# PiArcadeGPIO.net
KiCad netlist of a schematic drawn in Altium Designer
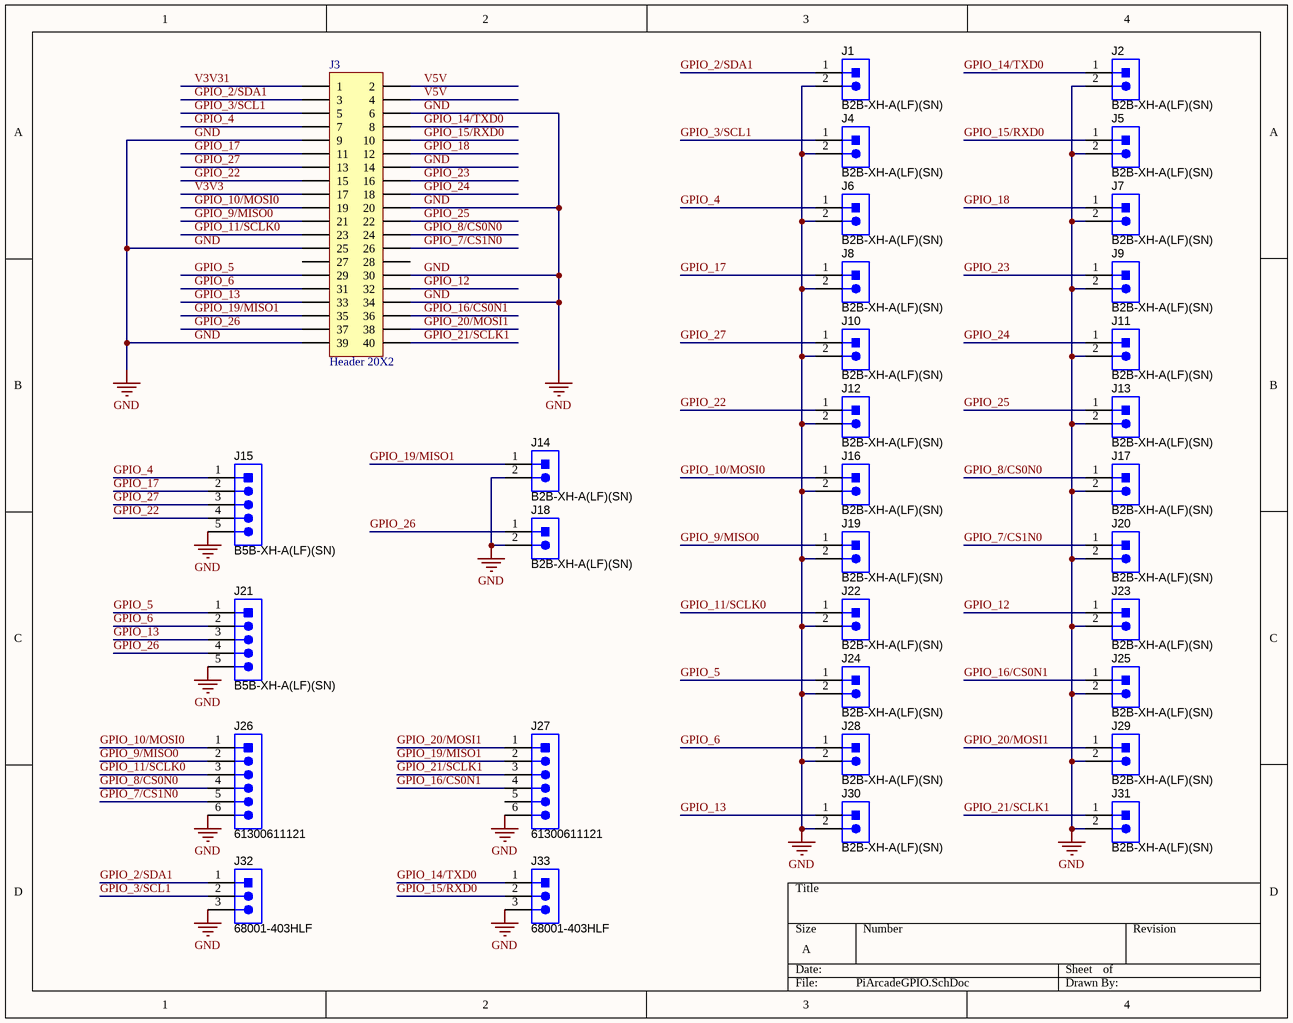
[diagram p0: PiArcadeGPIO.SchDoc]

(export (version "E")
  (design (tool "Eeschema 10.0.6"))
  (components
    (comp (ref "J1")
      (value "B2B-XH-A(LF)(SN)")
      (footprint "JST_B2B-XH-A")
      (description "Header (Shrouded), 2.5mm, 2x1, Tin, TH")
      (fields
        (field (name "MANUFACTURER") "JST Manufacturing")
        (field (name "SYMBOLCREATOR") "a0412235")
        (field (name "PUBLISHER") "Texas Instruments")
      )
      (libsource (lib "Connectors_Other") (part "B2B-XH-A(LF)(SN)"))
    )
    (comp (ref "J2")
      (value "B2B-XH-A(LF)(SN)")
      (footprint "JST_B2B-XH-A")
      (description "Header (Shrouded), 2.5mm, 2x1, Tin, TH")
      (fields
        (field (name "MANUFACTURER") "JST Manufacturing")
        (field (name "SYMBOLCREATOR") "a0412235")
        (field (name "PUBLISHER") "Texas Instruments")
      )
      (libsource (lib "Connectors_Other") (part "B2B-XH-A(LF)(SN)"))
    )
    (comp (ref "J3")
      (value "Header 20X2")
      (footprint "HDR2X20")
      (description "Header, 20-Pin, Dual row")
      (fields (field (name "PUBLISHER") "Altium Limited"))
      (libsource (lib "Miscellaneous Connectors") (part "Header 20X2"))
    )
    (comp (ref "J4")
      (value "B2B-XH-A(LF)(SN)")
      (footprint "JST_B2B-XH-A")
      (description "Header (Shrouded), 2.5mm, 2x1, Tin, TH")
      (fields
        (field (name "MANUFACTURER") "JST Manufacturing")
        (field (name "SYMBOLCREATOR") "a0412235")
        (field (name "PUBLISHER") "Texas Instruments")
      )
      (libsource (lib "Connectors_Other") (part "B2B-XH-A(LF)(SN)"))
    )
    (comp (ref "J5")
      (value "B2B-XH-A(LF)(SN)")
      (footprint "JST_B2B-XH-A")
      (description "Header (Shrouded), 2.5mm, 2x1, Tin, TH")
      (fields
        (field (name "MANUFACTURER") "JST Manufacturing")
        (field (name "SYMBOLCREATOR") "a0412235")
        (field (name "PUBLISHER") "Texas Instruments")
      )
      (libsource (lib "Connectors_Other") (part "B2B-XH-A(LF)(SN)"))
    )
    (comp (ref "J6")
      (value "B2B-XH-A(LF)(SN)")
      (footprint "JST_B2B-XH-A")
      (description "Header (Shrouded), 2.5mm, 2x1, Tin, TH")
      (fields
        (field (name "MANUFACTURER") "JST Manufacturing")
        (field (name "SYMBOLCREATOR") "a0412235")
        (field (name "PUBLISHER") "Texas Instruments")
      )
      (libsource (lib "Connectors_Other") (part "B2B-XH-A(LF)(SN)"))
    )
    (comp (ref "J7")
      (value "B2B-XH-A(LF)(SN)")
      (footprint "JST_B2B-XH-A")
      (description "Header (Shrouded), 2.5mm, 2x1, Tin, TH")
      (fields
        (field (name "MANUFACTURER") "JST Manufacturing")
        (field (name "SYMBOLCREATOR") "a0412235")
        (field (name "PUBLISHER") "Texas Instruments")
      )
      (libsource (lib "Connectors_Other") (part "B2B-XH-A(LF)(SN)"))
    )
    (comp (ref "J8")
      (value "B2B-XH-A(LF)(SN)")
      (footprint "JST_B2B-XH-A")
      (description "Header (Shrouded), 2.5mm, 2x1, Tin, TH")
      (fields
        (field (name "MANUFACTURER") "JST Manufacturing")
        (field (name "SYMBOLCREATOR") "a0412235")
        (field (name "PUBLISHER") "Texas Instruments")
      )
      (libsource (lib "Connectors_Other") (part "B2B-XH-A(LF)(SN)"))
    )
    (comp (ref "J9")
      (value "B2B-XH-A(LF)(SN)")
      (footprint "JST_B2B-XH-A")
      (description "Header (Shrouded), 2.5mm, 2x1, Tin, TH")
      (fields
        (field (name "MANUFACTURER") "JST Manufacturing")
        (field (name "SYMBOLCREATOR") "a0412235")
        (field (name "PUBLISHER") "Texas Instruments")
      )
      (libsource (lib "Connectors_Other") (part "B2B-XH-A(LF)(SN)"))
    )
    (comp (ref "J10")
      (value "B2B-XH-A(LF)(SN)")
      (footprint "JST_B2B-XH-A")
      (description "Header (Shrouded), 2.5mm, 2x1, Tin, TH")
      (fields
        (field (name "MANUFACTURER") "JST Manufacturing")
        (field (name "SYMBOLCREATOR") "a0412235")
        (field (name "PUBLISHER") "Texas Instruments")
      )
      (libsource (lib "Connectors_Other") (part "B2B-XH-A(LF)(SN)"))
    )
    (comp (ref "J11")
      (value "B2B-XH-A(LF)(SN)")
      (footprint "JST_B2B-XH-A")
      (description "Header (Shrouded), 2.5mm, 2x1, Tin, TH")
      (fields
        (field (name "MANUFACTURER") "JST Manufacturing")
        (field (name "SYMBOLCREATOR") "a0412235")
        (field (name "PUBLISHER") "Texas Instruments")
      )
      (libsource (lib "Connectors_Other") (part "B2B-XH-A(LF)(SN)"))
    )
    (comp (ref "J12")
      (value "B2B-XH-A(LF)(SN)")
      (footprint "JST_B2B-XH-A")
      (description "Header (Shrouded), 2.5mm, 2x1, Tin, TH")
      (fields
        (field (name "MANUFACTURER") "JST Manufacturing")
        (field (name "SYMBOLCREATOR") "a0412235")
        (field (name "PUBLISHER") "Texas Instruments")
      )
      (libsource (lib "Connectors_Other") (part "B2B-XH-A(LF)(SN)"))
    )
    (comp (ref "J13")
      (value "B2B-XH-A(LF)(SN)")
      (footprint "JST_B2B-XH-A")
      (description "Header (Shrouded), 2.5mm, 2x1, Tin, TH")
      (fields
        (field (name "MANUFACTURER") "JST Manufacturing")
        (field (name "SYMBOLCREATOR") "a0412235")
        (field (name "PUBLISHER") "Texas Instruments")
      )
      (libsource (lib "Connectors_Other") (part "B2B-XH-A(LF)(SN)"))
    )
    (comp (ref "J14")
      (value "B2B-XH-A(LF)(SN)")
      (footprint "JST_B2B-XH-A")
      (description "Header (Shrouded), 2.5mm, 2x1, Tin, TH")
      (fields
        (field (name "MANUFACTURER") "JST Manufacturing")
        (field (name "SYMBOLCREATOR") "a0412235")
        (field (name "PUBLISHER") "Texas Instruments")
      )
      (libsource (lib "Connectors_Other") (part "B2B-XH-A(LF)(SN)"))
    )
    (comp (ref "J15")
      (value "B5B-XH-A(LF)(SN)")
      (footprint "JST_B5B-XH-A")
      (description "Header(shrouded), 2.5mm, 5x1, Tin, TH")
      (fields
        (field (name "MANUFACTURER") "JST Manufacturing")
        (field (name "SYMBOLCREATOR") "a0412235")
        (field (name "PUBLISHER") "Texas Instruments")
      )
      (libsource (lib "Connectors_Other") (part "B5B-XH-A(LF)(SN)"))
    )
    (comp (ref "J16")
      (value "B2B-XH-A(LF)(SN)")
      (footprint "JST_B2B-XH-A")
      (description "Header (Shrouded), 2.5mm, 2x1, Tin, TH")
      (fields
        (field (name "MANUFACTURER") "JST Manufacturing")
        (field (name "SYMBOLCREATOR") "a0412235")
        (field (name "PUBLISHER") "Texas Instruments")
      )
      (libsource (lib "Connectors_Other") (part "B2B-XH-A(LF)(SN)"))
    )
    (comp (ref "J17")
      (value "B2B-XH-A(LF)(SN)")
      (footprint "JST_B2B-XH-A")
      (description "Header (Shrouded), 2.5mm, 2x1, Tin, TH")
      (fields
        (field (name "MANUFACTURER") "JST Manufacturing")
        (field (name "SYMBOLCREATOR") "a0412235")
        (field (name "PUBLISHER") "Texas Instruments")
      )
      (libsource (lib "Connectors_Other") (part "B2B-XH-A(LF)(SN)"))
    )
    (comp (ref "J18")
      (value "B2B-XH-A(LF)(SN)")
      (footprint "JST_B2B-XH-A")
      (description "Header (Shrouded), 2.5mm, 2x1, Tin, TH")
      (fields
        (field (name "MANUFACTURER") "JST Manufacturing")
        (field (name "SYMBOLCREATOR") "a0412235")
        (field (name "PUBLISHER") "Texas Instruments")
      )
      (libsource (lib "Connectors_Other") (part "B2B-XH-A(LF)(SN)"))
    )
    (comp (ref "J19")
      (value "B2B-XH-A(LF)(SN)")
      (footprint "JST_B2B-XH-A")
      (description "Header (Shrouded), 2.5mm, 2x1, Tin, TH")
      (fields
        (field (name "MANUFACTURER") "JST Manufacturing")
        (field (name "SYMBOLCREATOR") "a0412235")
        (field (name "PUBLISHER") "Texas Instruments")
      )
      (libsource (lib "Connectors_Other") (part "B2B-XH-A(LF)(SN)"))
    )
    (comp (ref "J20")
      (value "B2B-XH-A(LF)(SN)")
      (footprint "JST_B2B-XH-A")
      (description "Header (Shrouded), 2.5mm, 2x1, Tin, TH")
      (fields
        (field (name "MANUFACTURER") "JST Manufacturing")
        (field (name "SYMBOLCREATOR") "a0412235")
        (field (name "PUBLISHER") "Texas Instruments")
      )
      (libsource (lib "Connectors_Other") (part "B2B-XH-A(LF)(SN)"))
    )
    (comp (ref "J21")
      (value "B5B-XH-A(LF)(SN)")
      (footprint "JST_B5B-XH-A")
      (description "Header(shrouded), 2.5mm, 5x1, Tin, TH")
      (fields
        (field (name "MANUFACTURER") "JST Manufacturing")
        (field (name "SYMBOLCREATOR") "a0412235")
        (field (name "PUBLISHER") "Texas Instruments")
      )
      (libsource (lib "Connectors_Other") (part "B5B-XH-A(LF)(SN)"))
    )
    (comp (ref "J22")
      (value "B2B-XH-A(LF)(SN)")
      (footprint "JST_B2B-XH-A")
      (description "Header (Shrouded), 2.5mm, 2x1, Tin, TH")
      (fields
        (field (name "MANUFACTURER") "JST Manufacturing")
        (field (name "SYMBOLCREATOR") "a0412235")
        (field (name "PUBLISHER") "Texas Instruments")
      )
      (libsource (lib "Connectors_Other") (part "B2B-XH-A(LF)(SN)"))
    )
    (comp (ref "J23")
      (value "B2B-XH-A(LF)(SN)")
      (footprint "JST_B2B-XH-A")
      (description "Header (Shrouded), 2.5mm, 2x1, Tin, TH")
      (fields
        (field (name "MANUFACTURER") "JST Manufacturing")
        (field (name "SYMBOLCREATOR") "a0412235")
        (field (name "PUBLISHER") "Texas Instruments")
      )
      (libsource (lib "Connectors_Other") (part "B2B-XH-A(LF)(SN)"))
    )
    (comp (ref "J24")
      (value "B2B-XH-A(LF)(SN)")
      (footprint "JST_B2B-XH-A")
      (description "Header (Shrouded), 2.5mm, 2x1, Tin, TH")
      (fields
        (field (name "MANUFACTURER") "JST Manufacturing")
        (field (name "SYMBOLCREATOR") "a0412235")
        (field (name "PUBLISHER") "Texas Instruments")
      )
      (libsource (lib "Connectors_Other") (part "B2B-XH-A(LF)(SN)"))
    )
    (comp (ref "J25")
      (value "B2B-XH-A(LF)(SN)")
      (footprint "JST_B2B-XH-A")
      (description "Header (Shrouded), 2.5mm, 2x1, Tin, TH")
      (fields
        (field (name "MANUFACTURER") "JST Manufacturing")
        (field (name "SYMBOLCREATOR") "a0412235")
        (field (name "PUBLISHER") "Texas Instruments")
      )
      (libsource (lib "Connectors_Other") (part "B2B-XH-A(LF)(SN)"))
    )
    (comp (ref "J26")
      (value "61300611121")
      (footprint "WURTH_61300611121")
      (description "Header, 2.54 mm, 6x1, Gold, TH")
      (fields
        (field (name "MANUFACTURER") "Wurth Elektronik")
        (field (name "SYMBOLCREATOR") "a0412235")
        (field (name "PUBLISHER") "Texas Instruments")
      )
      (libsource (lib "Connectors_Other") (part "61300611121"))
    )
    (comp (ref "J27")
      (value "61300611121")
      (footprint "WURTH_61300611121")
      (description "Header, 2.54 mm, 6x1, Gold, TH")
      (fields
        (field (name "MANUFACTURER") "Wurth Elektronik")
        (field (name "SYMBOLCREATOR") "a0412235")
        (field (name "PUBLISHER") "Texas Instruments")
      )
      (libsource (lib "Connectors_Other") (part "61300611121"))
    )
    (comp (ref "J28")
      (value "B2B-XH-A(LF)(SN)")
      (footprint "JST_B2B-XH-A")
      (description "Header (Shrouded), 2.5mm, 2x1, Tin, TH")
      (fields
        (field (name "MANUFACTURER") "JST Manufacturing")
        (field (name "SYMBOLCREATOR") "a0412235")
        (field (name "PUBLISHER") "Texas Instruments")
      )
      (libsource (lib "Connectors_Other") (part "B2B-XH-A(LF)(SN)"))
    )
    (comp (ref "J29")
      (value "B2B-XH-A(LF)(SN)")
      (footprint "JST_B2B-XH-A")
      (description "Header (Shrouded), 2.5mm, 2x1, Tin, TH")
      (fields
        (field (name "MANUFACTURER") "JST Manufacturing")
        (field (name "SYMBOLCREATOR") "a0412235")
        (field (name "PUBLISHER") "Texas Instruments")
      )
      (libsource (lib "Connectors_Other") (part "B2B-XH-A(LF)(SN)"))
    )
    (comp (ref "J30")
      (value "B2B-XH-A(LF)(SN)")
      (footprint "JST_B2B-XH-A")
      (description "Header (Shrouded), 2.5mm, 2x1, Tin, TH")
      (fields
        (field (name "MANUFACTURER") "JST Manufacturing")
        (field (name "SYMBOLCREATOR") "a0412235")
        (field (name "PUBLISHER") "Texas Instruments")
      )
      (libsource (lib "Connectors_Other") (part "B2B-XH-A(LF)(SN)"))
    )
    (comp (ref "J31")
      (value "B2B-XH-A(LF)(SN)")
      (footprint "JST_B2B-XH-A")
      (description "Header (Shrouded), 2.5mm, 2x1, Tin, TH")
      (fields
        (field (name "MANUFACTURER") "JST Manufacturing")
        (field (name "SYMBOLCREATOR") "a0412235")
        (field (name "PUBLISHER") "Texas Instruments")
      )
      (libsource (lib "Connectors_Other") (part "B2B-XH-A(LF)(SN)"))
    )
    (comp (ref "J32")
      (value "68001-403HLF")
      (footprint "FCI_68001-403HLF")
      (description "Header, 2.54mm, 3x1, Tin, TH")
      (fields
        (field (name "MANUFACTURER") "FCI")
        (field (name "SYMBOLCREATOR") "a0799628")
        (field (name "PUBLISHER") "Texas Instruments")
      )
      (libsource (lib "Connectors_Other") (part "68001-403HLF"))
    )
    (comp (ref "J33")
      (value "68001-403HLF")
      (footprint "FCI_68001-403HLF")
      (description "Header, 2.54mm, 3x1, Tin, TH")
      (fields
        (field (name "MANUFACTURER") "FCI")
        (field (name "SYMBOLCREATOR") "a0799628")
        (field (name "PUBLISHER") "Texas Instruments")
      )
      (libsource (lib "Connectors_Other") (part "68001-403HLF"))
    )
  )
  (nets
    (net (code "1") (name "/GPIO_2{slash}SDA1") (class "Default")
      (node (ref "J1") (pin "1") (pinfunction "1_1") (pintype "passive"))
      (node (ref "J3") (pin "3") (pinfunction "3_3") (pintype "passive"))
      (node (ref "J32") (pin "1") (pinfunction "1_1") (pintype "passive"))
    )
    (net (code "2") (name "/GPIO_3{slash}SCL1") (class "Default")
      (node (ref "J3") (pin "5") (pinfunction "5_5") (pintype "passive"))
      (node (ref "J32") (pin "2") (pinfunction "2_2") (pintype "passive"))
      (node (ref "J4") (pin "1") (pinfunction "1_1") (pintype "passive"))
    )
    (net (code "3") (name "/GPIO_4") (class "Default")
      (node (ref "J15") (pin "1") (pinfunction "1_1") (pintype "passive"))
      (node (ref "J3") (pin "7") (pinfunction "7_7") (pintype "passive"))
      (node (ref "J6") (pin "1") (pinfunction "1_1") (pintype "passive"))
    )
    (net (code "4") (name "/GPIO_5") (class "Default")
      (node (ref "J21") (pin "1") (pinfunction "1_1") (pintype "passive"))
      (node (ref "J24") (pin "1") (pinfunction "1_1") (pintype "passive"))
      (node (ref "J3") (pin "29") (pinfunction "29_29") (pintype "passive"))
    )
    (net (code "5") (name "/GPIO_6") (class "Default")
      (node (ref "J21") (pin "2") (pinfunction "2_2") (pintype "passive"))
      (node (ref "J28") (pin "1") (pinfunction "1_1") (pintype "passive"))
      (node (ref "J3") (pin "31") (pinfunction "31_31") (pintype "passive"))
    )
    (net (code "6") (name "/GPIO_7{slash}CS1N0") (class "Default")
      (node (ref "J20") (pin "1") (pinfunction "1_1") (pintype "passive"))
      (node (ref "J26") (pin "5") (pinfunction "5_5") (pintype "passive"))
      (node (ref "J3") (pin "26") (pinfunction "26_26") (pintype "passive"))
    )
    (net (code "7") (name "/GPIO_8{slash}CS0N0") (class "Default")
      (node (ref "J17") (pin "1") (pinfunction "1_1") (pintype "passive"))
      (node (ref "J26") (pin "4") (pinfunction "4_4") (pintype "passive"))
      (node (ref "J3") (pin "24") (pinfunction "24_24") (pintype "passive"))
    )
    (net (code "8") (name "/GPIO_9{slash}MISO0") (class "Default")
      (node (ref "J19") (pin "1") (pinfunction "1_1") (pintype "passive"))
      (node (ref "J26") (pin "2") (pinfunction "2_2") (pintype "passive"))
      (node (ref "J3") (pin "21") (pinfunction "21_21") (pintype "passive"))
    )
    (net (code "9") (name "/GPIO_10{slash}MOSI0") (class "Default")
      (node (ref "J16") (pin "1") (pinfunction "1_1") (pintype "passive"))
      (node (ref "J26") (pin "1") (pinfunction "1_1") (pintype "passive"))
      (node (ref "J3") (pin "19") (pinfunction "19_19") (pintype "passive"))
    )
    (net (code "10") (name "/GPIO_11{slash}SCLK0") (class "Default")
      (node (ref "J22") (pin "1") (pinfunction "1_1") (pintype "passive"))
      (node (ref "J26") (pin "3") (pinfunction "3_3") (pintype "passive"))
      (node (ref "J3") (pin "23") (pinfunction "23_23") (pintype "passive"))
    )
    (net (code "11") (name "/GPIO_12") (class "Default")
      (node (ref "J23") (pin "1") (pinfunction "1_1") (pintype "passive"))
      (node (ref "J3") (pin "32") (pinfunction "32_32") (pintype "passive"))
    )
    (net (code "12") (name "/GPIO_13") (class "Default")
      (node (ref "J21") (pin "3") (pinfunction "3_3") (pintype "passive"))
      (node (ref "J3") (pin "33") (pinfunction "33_33") (pintype "passive"))
      (node (ref "J30") (pin "1") (pinfunction "1_1") (pintype "passive"))
    )
    (net (code "13") (name "/GPIO_14{slash}TXD0") (class "Default")
      (node (ref "J2") (pin "1") (pinfunction "1_1") (pintype "passive"))
      (node (ref "J3") (pin "8") (pinfunction "8_8") (pintype "passive"))
      (node (ref "J33") (pin "1") (pinfunction "1_1") (pintype "passive"))
    )
    (net (code "14") (name "/GPIO_15{slash}RXD0") (class "Default")
      (node (ref "J3") (pin "10") (pinfunction "10_10") (pintype "passive"))
      (node (ref "J33") (pin "2") (pinfunction "2_2") (pintype "passive"))
      (node (ref "J5") (pin "1") (pinfunction "1_1") (pintype "passive"))
    )
    (net (code "15") (name "/GPIO_16{slash}CS0N1") (class "Default")
      (node (ref "J25") (pin "1") (pinfunction "1_1") (pintype "passive"))
      (node (ref "J27") (pin "4") (pinfunction "4_4") (pintype "passive"))
      (node (ref "J3") (pin "36") (pinfunction "36_36") (pintype "passive"))
    )
    (net (code "16") (name "/GPIO_17") (class "Default")
      (node (ref "J15") (pin "2") (pinfunction "2_2") (pintype "passive"))
      (node (ref "J3") (pin "11") (pinfunction "11_11") (pintype "passive"))
      (node (ref "J8") (pin "1") (pinfunction "1_1") (pintype "passive"))
    )
    (net (code "17") (name "/GPIO_18") (class "Default")
      (node (ref "J3") (pin "12") (pinfunction "12_12") (pintype "passive"))
      (node (ref "J7") (pin "1") (pinfunction "1_1") (pintype "passive"))
    )
    (net (code "18") (name "/GPIO_19{slash}MISO1") (class "Default")
      (node (ref "J14") (pin "1") (pinfunction "1_1") (pintype "passive"))
      (node (ref "J27") (pin "2") (pinfunction "2_2") (pintype "passive"))
      (node (ref "J3") (pin "35") (pinfunction "35_35") (pintype "passive"))
    )
    (net (code "19") (name "/GPIO_20{slash}MOSI1") (class "Default")
      (node (ref "J27") (pin "1") (pinfunction "1_1") (pintype "passive"))
      (node (ref "J29") (pin "1") (pinfunction "1_1") (pintype "passive"))
      (node (ref "J3") (pin "38") (pinfunction "38_38") (pintype "passive"))
    )
    (net (code "20") (name "/GPIO_21{slash}SCLK1") (class "Default")
      (node (ref "J27") (pin "3") (pinfunction "3_3") (pintype "passive"))
      (node (ref "J3") (pin "40") (pinfunction "40_40") (pintype "passive"))
      (node (ref "J31") (pin "1") (pinfunction "1_1") (pintype "passive"))
    )
    (net (code "21") (name "/GPIO_22") (class "Default")
      (node (ref "J12") (pin "1") (pinfunction "1_1") (pintype "passive"))
      (node (ref "J15") (pin "4") (pinfunction "4_4") (pintype "passive"))
      (node (ref "J3") (pin "15") (pinfunction "15_15") (pintype "passive"))
    )
    (net (code "22") (name "/GPIO_23") (class "Default")
      (node (ref "J3") (pin "16") (pinfunction "16_16") (pintype "passive"))
      (node (ref "J9") (pin "1") (pinfunction "1_1") (pintype "passive"))
    )
    (net (code "23") (name "/GPIO_24") (class "Default")
      (node (ref "J11") (pin "1") (pinfunction "1_1") (pintype "passive"))
      (node (ref "J3") (pin "18") (pinfunction "18_18") (pintype "passive"))
    )
    (net (code "24") (name "/GPIO_25") (class "Default")
      (node (ref "J13") (pin "1") (pinfunction "1_1") (pintype "passive"))
      (node (ref "J3") (pin "22") (pinfunction "22_22") (pintype "passive"))
    )
    (net (code "25") (name "/GPIO_26") (class "Default")
      (node (ref "J18") (pin "1") (pinfunction "1_1") (pintype "passive"))
      (node (ref "J21") (pin "4") (pinfunction "4_4") (pintype "passive"))
      (node (ref "J3") (pin "37") (pinfunction "37_37") (pintype "passive"))
    )
    (net (code "26") (name "/GPIO_27") (class "Default")
      (node (ref "J10") (pin "1") (pinfunction "1_1") (pintype "passive"))
      (node (ref "J15") (pin "3") (pinfunction "3_3") (pintype "passive"))
      (node (ref "J3") (pin "13") (pinfunction "13_13") (pintype "passive"))
    )
    (net (code "27") (name "/V3V3") (class "Default")
      (node (ref "J3") (pin "17") (pinfunction "17_17") (pintype "passive"))
    )
    (net (code "28") (name "/V3V31") (class "Default")
      (node (ref "J3") (pin "1") (pinfunction "1_1") (pintype "passive"))
    )
    (net (code "29") (name "/V5V") (class "Default")
      (node (ref "J3") (pin "2") (pinfunction "2_2") (pintype "passive"))
      (node (ref "J3") (pin "4") (pinfunction "4_4") (pintype "passive"))
    )
    (net (code "30") (name "GND") (class "Default")
      (node (ref "J1") (pin "2") (pinfunction "2_2") (pintype "passive"))
      (node (ref "J10") (pin "2") (pinfunction "2_2") (pintype "passive"))
      (node (ref "J11") (pin "2") (pinfunction "2_2") (pintype "passive"))
      (node (ref "J12") (pin "2") (pinfunction "2_2") (pintype "passive"))
      (node (ref "J13") (pin "2") (pinfunction "2_2") (pintype "passive"))
      (node (ref "J14") (pin "2") (pinfunction "2_2") (pintype "passive"))
      (node (ref "J15") (pin "5") (pinfunction "5_5") (pintype "passive"))
      (node (ref "J16") (pin "2") (pinfunction "2_2") (pintype "passive"))
      (node (ref "J17") (pin "2") (pinfunction "2_2") (pintype "passive"))
      (node (ref "J18") (pin "2") (pinfunction "2_2") (pintype "passive"))
      (node (ref "J19") (pin "2") (pinfunction "2_2") (pintype "passive"))
      (node (ref "J2") (pin "2") (pinfunction "2_2") (pintype "passive"))
      (node (ref "J20") (pin "2") (pinfunction "2_2") (pintype "passive"))
      (node (ref "J21") (pin "5") (pinfunction "5_5") (pintype "passive"))
      (node (ref "J22") (pin "2") (pinfunction "2_2") (pintype "passive"))
      (node (ref "J23") (pin "2") (pinfunction "2_2") (pintype "passive"))
      (node (ref "J24") (pin "2") (pinfunction "2_2") (pintype "passive"))
      (node (ref "J25") (pin "2") (pinfunction "2_2") (pintype "passive"))
      (node (ref "J26") (pin "6") (pinfunction "6_6") (pintype "passive"))
      (node (ref "J27") (pin "6") (pinfunction "6_6") (pintype "passive"))
      (node (ref "J28") (pin "2") (pinfunction "2_2") (pintype "passive"))
      (node (ref "J29") (pin "2") (pinfunction "2_2") (pintype "passive"))
      (node (ref "J3") (pin "14") (pinfunction "14_14") (pintype "passive"))
      (node (ref "J3") (pin "20") (pinfunction "20_20") (pintype "passive"))
      (node (ref "J3") (pin "25") (pinfunction "25_25") (pintype "passive"))
      (node (ref "J3") (pin "30") (pinfunction "30_30") (pintype "passive"))
      (node (ref "J3") (pin "34") (pinfunction "34_34") (pintype "passive"))
      (node (ref "J3") (pin "39") (pinfunction "39_39") (pintype "passive"))
      (node (ref "J3") (pin "6") (pinfunction "6_6") (pintype "passive"))
      (node (ref "J3") (pin "9") (pinfunction "9_9") (pintype "passive"))
      (node (ref "J30") (pin "2") (pinfunction "2_2") (pintype "passive"))
      (node (ref "J31") (pin "2") (pinfunction "2_2") (pintype "passive"))
      (node (ref "J32") (pin "3") (pinfunction "3_3") (pintype "passive"))
      (node (ref "J33") (pin "3") (pinfunction "3_3") (pintype "passive"))
      (node (ref "J4") (pin "2") (pinfunction "2_2") (pintype "passive"))
      (node (ref "J5") (pin "2") (pinfunction "2_2") (pintype "passive"))
      (node (ref "J6") (pin "2") (pinfunction "2_2") (pintype "passive"))
      (node (ref "J7") (pin "2") (pinfunction "2_2") (pintype "passive"))
      (node (ref "J8") (pin "2") (pinfunction "2_2") (pintype "passive"))
      (node (ref "J9") (pin "2") (pinfunction "2_2") (pintype "passive"))
    )
    (net (code "31") (name "unconnected-(J3-Pad27)") (class "Default")
      (node (ref "J3") (pin "27") (pinfunction "27_27") (pintype "passive"))
    )
    (net (code "32") (name "unconnected-(J3-Pad28)") (class "Default")
      (node (ref "J3") (pin "28") (pinfunction "28_28") (pintype "passive"))
    )
    (net (code "33") (name "unconnected-(J27-Pad5)") (class "Default")
      (node (ref "J27") (pin "5") (pinfunction "5_5") (pintype "passive"))
    )
  )
)
